# MRCS-cpNode.net
KiCad netlist of a schematic drawn in EAGLE
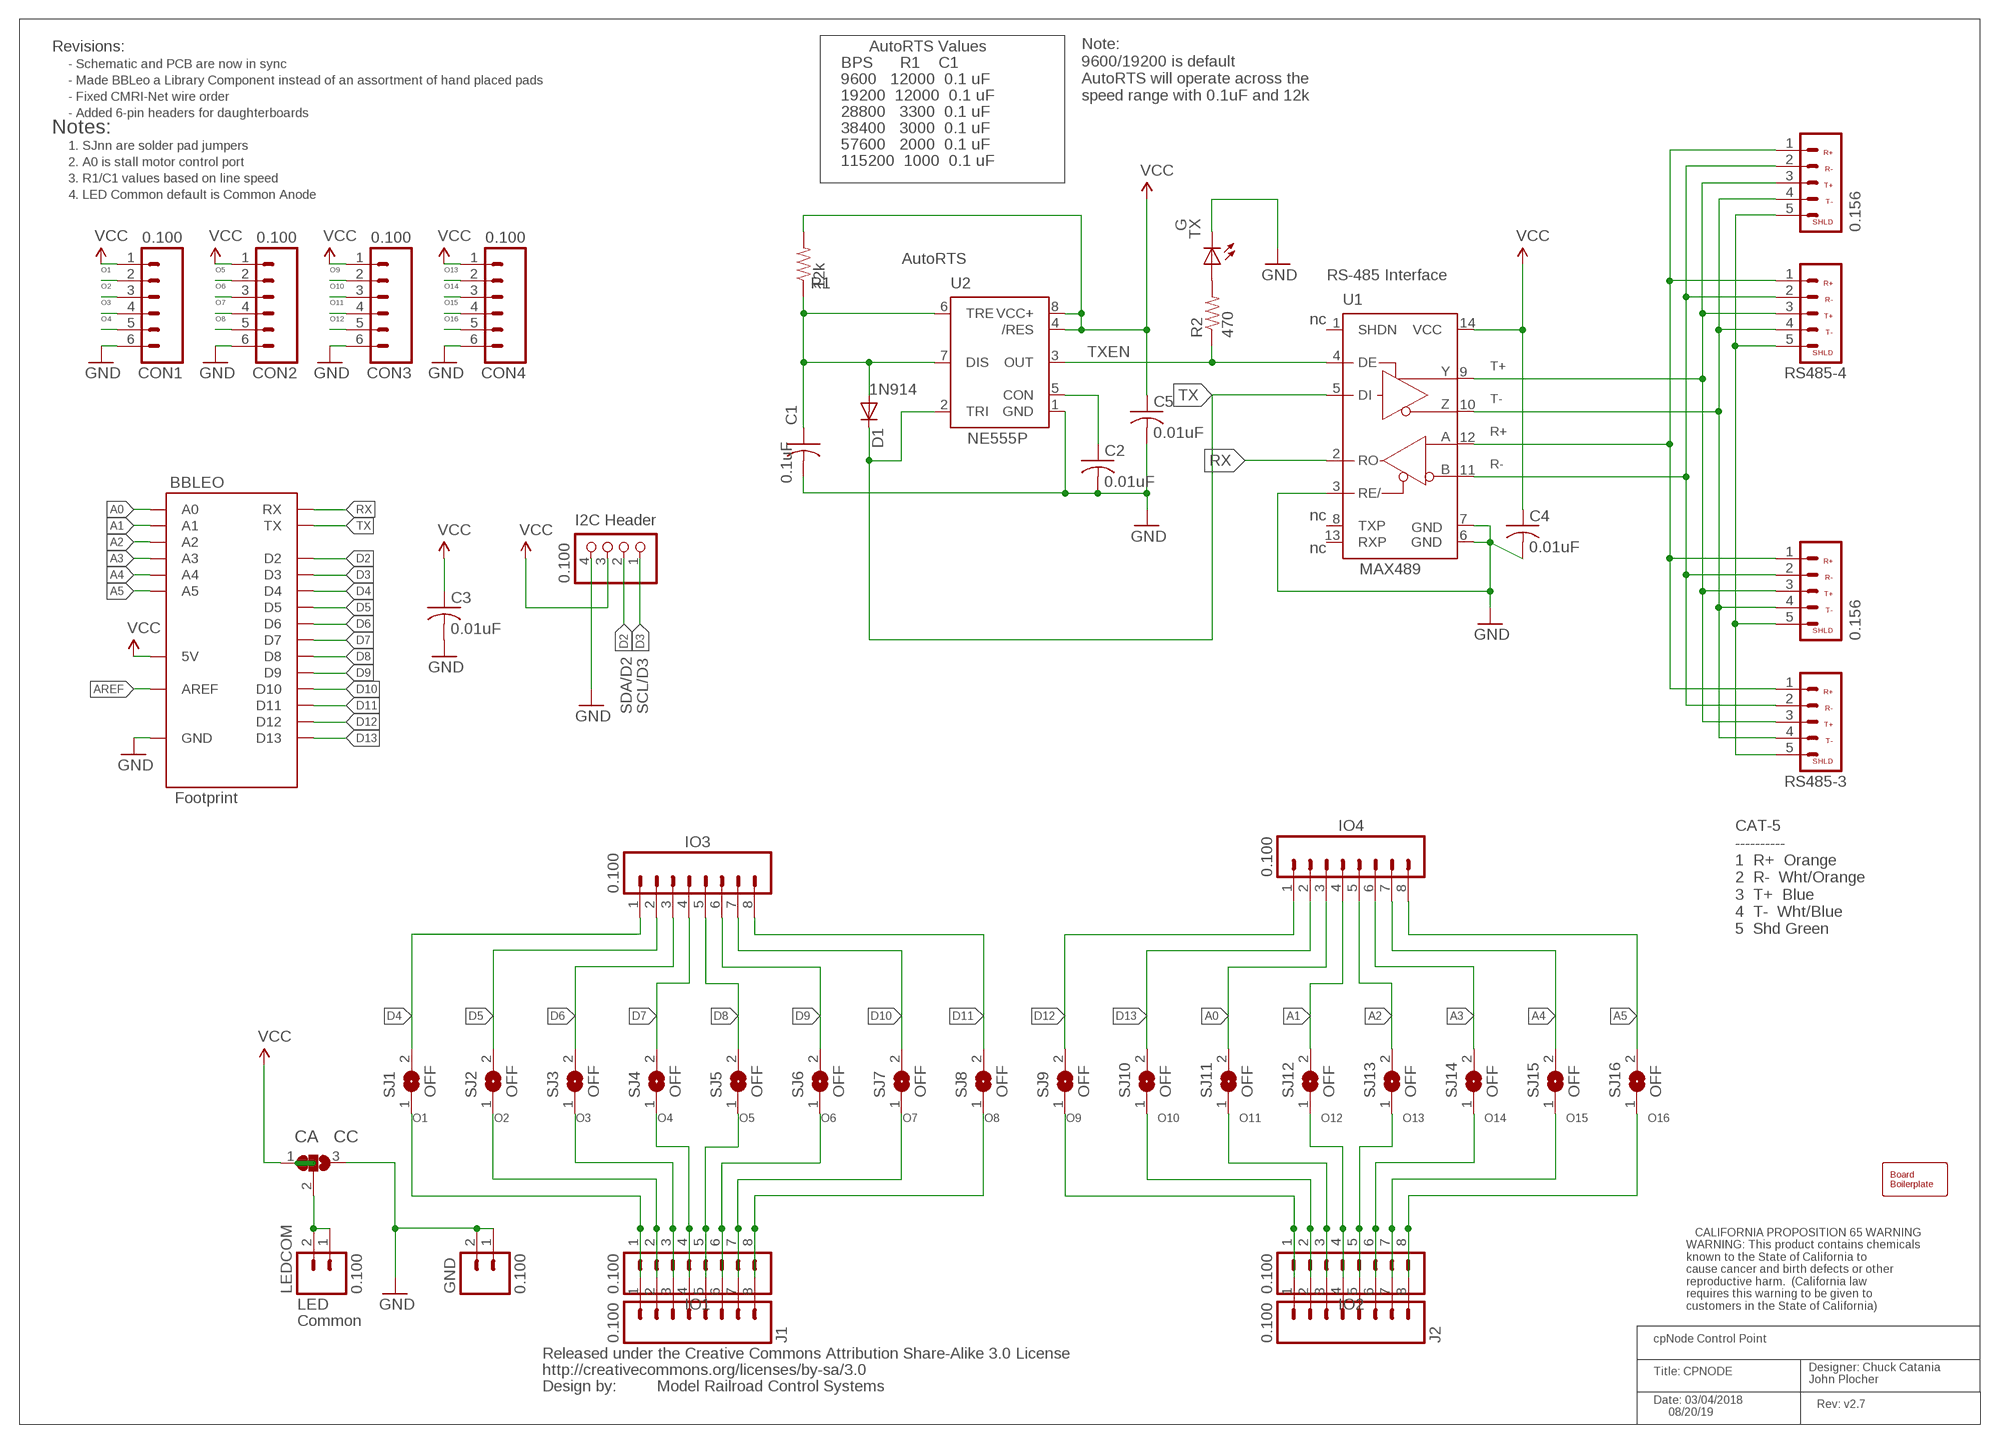
[diagram p0: schematic, sheet 1]

(export (version "E")
  (design (tool "Eeschema 10.0.6"))
  (components
    (comp (ref "BBLEO")
      (value "Footprint")
      (footprint "eagle-import:ARDUINO-BBLEO")
      (libsource (lib "eagle-import") (part "ARDUINO-BBLEO"))
    )
    (comp (ref "BOARD1")
      (value "BOARD")
      (footprint "eagle-import:BOARD-DINRAIL-2.71IN-MRCS")
      (libsource (lib "eagle-import") (part "BOARD69X100MRCS"))
    )
    (comp (ref "C1")
      (value "0.1uF")
      (footprint "eagle-import:C-PTH-0.100")
      (libsource (lib "eagle-import") (part "CAPPTH2"))
    )
    (comp (ref "C2")
      (value "0.01uF")
      (footprint "eagle-import:C-PTH-0.100")
      (libsource (lib "eagle-import") (part "CAPPTH2"))
    )
    (comp (ref "C3")
      (value "0.01uF")
      (footprint "eagle-import:C-PTH-0.100")
      (libsource (lib "eagle-import") (part "CAPPTH2"))
    )
    (comp (ref "C4")
      (value "0.01uF")
      (footprint "eagle-import:C-PTH-0.100")
      (libsource (lib "eagle-import") (part "CAPPTH2"))
    )
    (comp (ref "C5")
      (value "0.01uF")
      (footprint "eagle-import:C-PTH-0.100")
      (libsource (lib "eagle-import") (part "CAPPTH2"))
    )
    (comp (ref "CON1")
      (value "0.100")
      (footprint "eagle-import:1X06-SIP_LOCK")
      (libsource (lib "eagle-import") (part "CONNECTOR-M06SIP_LOCK"))
    )
    (comp (ref "CON2")
      (value "0.100")
      (footprint "eagle-import:1X06-SIP_LOCK")
      (libsource (lib "eagle-import") (part "CONNECTOR-M06SIP_LOCK"))
    )
    (comp (ref "CON3")
      (value "0.100")
      (footprint "eagle-import:1X06-SIP_LOCK")
      (libsource (lib "eagle-import") (part "CONNECTOR-M06SIP_LOCK"))
    )
    (comp (ref "CON4")
      (value "0.100")
      (footprint "eagle-import:1X06-SIP_LOCK")
      (libsource (lib "eagle-import") (part "CONNECTOR-M06SIP_LOCK"))
    )
    (comp (ref "D1")
      (value "1N4148")
      (footprint "eagle-import:DIODE-1N4148")
      (libsource (lib "eagle-import") (part "DIODE1N4148"))
    )
    (comp (ref "GND")
      (value "0.100")
      (footprint "eagle-import:MOLEX-1X2_LOCK")
      (libsource (lib "eagle-import") (part "M02POLAR_LOCK"))
    )
    (comp (ref "I2CHDR")
      (value "0.100")
      (footprint "eagle-import:1X04_90")
      (libsource (lib "eagle-import") (part "PINHD-1X4/90"))
    )
    (comp (ref "IO1")
      (value "0.100")
      (footprint "eagle-import:1X08")
      (libsource (lib "eagle-import") (part "M081X08"))
    )
    (comp (ref "IO2")
      (value "0.100")
      (footprint "eagle-import:1X08")
      (libsource (lib "eagle-import") (part "M081X08"))
    )
    (comp (ref "IO3")
      (value "0.100")
      (footprint "eagle-import:1X08")
      (libsource (lib "eagle-import") (part "M081X08"))
    )
    (comp (ref "IO4")
      (value "0.100")
      (footprint "eagle-import:1X08")
      (libsource (lib "eagle-import") (part "M081X08"))
    )
    (comp (ref "J1")
      (value "0.100")
      (footprint "eagle-import:1X08_LOCK_LONGPADS")
      (libsource (lib "eagle-import") (part "CONNECTOR-M08LOCK_LONGPADS"))
    )
    (comp (ref "J2")
      (value "0.100")
      (footprint "eagle-import:1X08_LOCK_LONGPADS")
      (libsource (lib "eagle-import") (part "CONNECTOR-M08LOCK_LONGPADS"))
    )
    (comp (ref "LEDCOM")
      (value "0.100")
      (footprint "eagle-import:MOLEX-1X2_LOCK")
      (libsource (lib "eagle-import") (part "M02POLAR_LOCK"))
    )
    (comp (ref "P1")
      (value "CA CC")
      (footprint "eagle-import:3P-SMD-2X4.8")
      (libsource (lib "eagle-import") (part "PAD-SOLDERJUMPER-2WAYT"))
    )
    (comp (ref "R1")
      (value "12k")
      (footprint "eagle-import:AXIAL-0.4-RES")
      (libsource (lib "eagle-import") (part "RPTH04"))
    )
    (comp (ref "R2")
      (value "470")
      (footprint "eagle-import:AXIAL-0.4-RES")
      (libsource (lib "eagle-import") (part "RPTH04"))
    )
    (comp (ref "RS485-1")
      (value "0.156")
      (footprint "eagle-import:KK-156-5")
      (libsource (lib "eagle-import") (part "CONNECTOR-CMRINET.156"))
    )
    (comp (ref "RS485-2")
      (value "0.156")
      (footprint "eagle-import:KK-156-5")
      (libsource (lib "eagle-import") (part "CONNECTOR-CMRINET.156"))
    )
    (comp (ref "RS485-3")
      (value "3.5mm")
      (footprint "eagle-import:CMRINET-3.5MM")
      (libsource (lib "eagle-import") (part "CONNECTOR-CMRINET3.5MM"))
    )
    (comp (ref "RS485-4")
      (value "3.5mm")
      (footprint "eagle-import:CMRINET-3.5MM")
      (libsource (lib "eagle-import") (part "CONNECTOR-CMRINET3.5MM"))
    )
    (comp (ref "SJ1")
      (value "OFF")
      (footprint "eagle-import:SJ")
      (libsource (lib "eagle-import") (part "SJ"))
    )
    (comp (ref "SJ2")
      (value "OFF")
      (footprint "eagle-import:SJ")
      (libsource (lib "eagle-import") (part "SJ"))
    )
    (comp (ref "SJ3")
      (value "OFF")
      (footprint "eagle-import:SJ")
      (libsource (lib "eagle-import") (part "SJ"))
    )
    (comp (ref "SJ4")
      (value "OFF")
      (footprint "eagle-import:SJ")
      (libsource (lib "eagle-import") (part "SJ"))
    )
    (comp (ref "SJ5")
      (value "OFF")
      (footprint "eagle-import:SJ")
      (libsource (lib "eagle-import") (part "SJ"))
    )
    (comp (ref "SJ6")
      (value "OFF")
      (footprint "eagle-import:SJ")
      (libsource (lib "eagle-import") (part "SJ"))
    )
    (comp (ref "SJ7")
      (value "OFF")
      (footprint "eagle-import:SJ")
      (libsource (lib "eagle-import") (part "SJ"))
    )
    (comp (ref "SJ8")
      (value "OFF")
      (footprint "eagle-import:SJ")
      (libsource (lib "eagle-import") (part "SJ"))
    )
    (comp (ref "SJ9")
      (value "OFF")
      (footprint "eagle-import:SJ")
      (libsource (lib "eagle-import") (part "SJ"))
    )
    (comp (ref "SJ10")
      (value "OFF")
      (footprint "eagle-import:SJ")
      (libsource (lib "eagle-import") (part "SJ"))
    )
    (comp (ref "SJ11")
      (value "OFF")
      (footprint "eagle-import:SJ")
      (libsource (lib "eagle-import") (part "SJ"))
    )
    (comp (ref "SJ12")
      (value "OFF")
      (footprint "eagle-import:SJ")
      (libsource (lib "eagle-import") (part "SJ"))
    )
    (comp (ref "SJ13")
      (value "OFF")
      (footprint "eagle-import:SJ")
      (libsource (lib "eagle-import") (part "SJ"))
    )
    (comp (ref "SJ14")
      (value "OFF")
      (footprint "eagle-import:SJ")
      (libsource (lib "eagle-import") (part "SJ"))
    )
    (comp (ref "SJ15")
      (value "OFF")
      (footprint "eagle-import:SJ")
      (libsource (lib "eagle-import") (part "SJ"))
    )
    (comp (ref "SJ16")
      (value "OFF")
      (footprint "eagle-import:SJ")
      (libsource (lib "eagle-import") (part "SJ"))
    )
    (comp (ref "TX")
      (value "G")
      (footprint "eagle-import:LED3MM")
      (libsource (lib "eagle-import") (part "LEDLED3MM"))
    )
    (comp (ref "U$1")
      (value "CREATIVE_COMMONS")
      (footprint "eagle-import:CREATIVE_COMMONS")
      (libsource (lib "eagle-import") (part "CREATIVE_COMMONS"))
    )
    (comp (ref "U$2")
      (value "Prop65")
      (footprint "eagle-import:CA-PROP65WARNING")
      (libsource (lib "eagle-import") (part "CA-PROP65WARNING"))
    )
    (comp (ref "U1")
      (value "MAX3465CPD")
      (footprint "eagle-import:DIL14")
      (fields (field (name "MPN") "MAX3465CPD+"))
      (libsource (lib "eagle-import") (part "MAX346PD5C"))
    )
    (comp (ref "U2")
      (value "NE555P")
      (footprint "eagle-import:DIL-08")
      (fields (field (name "MF") "Arrow Electronics") (field (name "MPN") "NE555N"))
      (libsource (lib "eagle-import") (part "NE555P"))
    )
  )
  (nets
    (net (code "1") (name "/O1") (class "Default")
      (node (ref "CON1") (pin "2") (pinfunction "2_2") (pintype "passive"))
      (node (ref "IO1") (pin "1") (pinfunction "1_1") (pintype "passive"))
      (node (ref "J1") (pin "1") (pinfunction "1_1") (pintype "passive"))
      (node (ref "SJ1") (pin "1") (pinfunction "1_1") (pintype "passive"))
    )
    (net (code "2") (name "/O2") (class "Default")
      (node (ref "CON1") (pin "3") (pinfunction "3_3") (pintype "passive"))
      (node (ref "IO1") (pin "2") (pinfunction "2_2") (pintype "passive"))
      (node (ref "J1") (pin "2") (pinfunction "2_2") (pintype "passive"))
      (node (ref "SJ2") (pin "1") (pinfunction "1_1") (pintype "passive"))
    )
    (net (code "3") (name "/O3") (class "Default")
      (node (ref "CON1") (pin "4") (pinfunction "4_4") (pintype "passive"))
      (node (ref "IO1") (pin "3") (pinfunction "3_3") (pintype "passive"))
      (node (ref "J1") (pin "3") (pinfunction "3_3") (pintype "passive"))
      (node (ref "SJ3") (pin "1") (pinfunction "1_1") (pintype "passive"))
    )
    (net (code "4") (name "/O4") (class "Default")
      (node (ref "CON1") (pin "5") (pinfunction "5_5") (pintype "passive"))
      (node (ref "IO1") (pin "4") (pinfunction "4_4") (pintype "passive"))
      (node (ref "J1") (pin "4") (pinfunction "4_4") (pintype "passive"))
      (node (ref "SJ4") (pin "1") (pinfunction "1_1") (pintype "passive"))
    )
    (net (code "5") (name "/O5") (class "Default")
      (node (ref "CON2") (pin "2") (pinfunction "2_2") (pintype "passive"))
      (node (ref "IO1") (pin "5") (pinfunction "5_5") (pintype "passive"))
      (node (ref "J1") (pin "5") (pinfunction "5_5") (pintype "passive"))
      (node (ref "SJ5") (pin "1") (pinfunction "1_1") (pintype "passive"))
    )
    (net (code "6") (name "/O6") (class "Default")
      (node (ref "CON2") (pin "3") (pinfunction "3_3") (pintype "passive"))
      (node (ref "IO1") (pin "6") (pinfunction "6_6") (pintype "passive"))
      (node (ref "J1") (pin "6") (pinfunction "6_6") (pintype "passive"))
      (node (ref "SJ6") (pin "1") (pinfunction "1_1") (pintype "passive"))
    )
    (net (code "7") (name "/O7") (class "Default")
      (node (ref "CON2") (pin "4") (pinfunction "4_4") (pintype "passive"))
      (node (ref "IO1") (pin "7") (pinfunction "7_7") (pintype "passive"))
      (node (ref "J1") (pin "7") (pinfunction "7_7") (pintype "passive"))
      (node (ref "SJ7") (pin "1") (pinfunction "1_1") (pintype "passive"))
    )
    (net (code "8") (name "/O8") (class "Default")
      (node (ref "CON2") (pin "5") (pinfunction "5_5") (pintype "passive"))
      (node (ref "IO1") (pin "8") (pinfunction "8_8") (pintype "passive"))
      (node (ref "J1") (pin "8") (pinfunction "8_8") (pintype "passive"))
      (node (ref "SJ8") (pin "1") (pinfunction "1_1") (pintype "passive"))
    )
    (net (code "9") (name "/O9") (class "Default")
      (node (ref "CON3") (pin "2") (pinfunction "2_2") (pintype "passive"))
      (node (ref "IO2") (pin "1") (pinfunction "1_1") (pintype "passive"))
      (node (ref "J2") (pin "1") (pinfunction "1_1") (pintype "passive"))
      (node (ref "SJ9") (pin "1") (pinfunction "1_1") (pintype "passive"))
    )
    (net (code "10") (name "/O10") (class "Default")
      (node (ref "CON3") (pin "3") (pinfunction "3_3") (pintype "passive"))
      (node (ref "IO2") (pin "2") (pinfunction "2_2") (pintype "passive"))
      (node (ref "J2") (pin "2") (pinfunction "2_2") (pintype "passive"))
      (node (ref "SJ10") (pin "1") (pinfunction "1_1") (pintype "passive"))
    )
    (net (code "11") (name "/O11") (class "Default")
      (node (ref "CON3") (pin "4") (pinfunction "4_4") (pintype "passive"))
      (node (ref "IO2") (pin "3") (pinfunction "3_3") (pintype "passive"))
      (node (ref "J2") (pin "3") (pinfunction "3_3") (pintype "passive"))
      (node (ref "SJ11") (pin "1") (pinfunction "1_1") (pintype "passive"))
    )
    (net (code "12") (name "/O12") (class "Default")
      (node (ref "CON3") (pin "5") (pinfunction "5_5") (pintype "passive"))
      (node (ref "IO2") (pin "4") (pinfunction "4_4") (pintype "passive"))
      (node (ref "J2") (pin "4") (pinfunction "4_4") (pintype "passive"))
      (node (ref "SJ12") (pin "1") (pinfunction "1_1") (pintype "passive"))
    )
    (net (code "13") (name "/O13") (class "Default")
      (node (ref "CON4") (pin "2") (pinfunction "2_2") (pintype "passive"))
      (node (ref "IO2") (pin "5") (pinfunction "5_5") (pintype "passive"))
      (node (ref "J2") (pin "5") (pinfunction "5_5") (pintype "passive"))
      (node (ref "SJ13") (pin "1") (pinfunction "1_1") (pintype "passive"))
    )
    (net (code "14") (name "/O14") (class "Default")
      (node (ref "CON4") (pin "3") (pinfunction "3_3") (pintype "passive"))
      (node (ref "IO2") (pin "6") (pinfunction "6_6") (pintype "passive"))
      (node (ref "J2") (pin "6") (pinfunction "6_6") (pintype "passive"))
      (node (ref "SJ14") (pin "1") (pinfunction "1_1") (pintype "passive"))
    )
    (net (code "15") (name "/O15") (class "Default")
      (node (ref "CON4") (pin "4") (pinfunction "4_4") (pintype "passive"))
      (node (ref "IO2") (pin "7") (pinfunction "7_7") (pintype "passive"))
      (node (ref "J2") (pin "7") (pinfunction "7_7") (pintype "passive"))
      (node (ref "SJ15") (pin "1") (pinfunction "1_1") (pintype "passive"))
    )
    (net (code "16") (name "/O16") (class "Default")
      (node (ref "CON4") (pin "5") (pinfunction "5_5") (pintype "passive"))
      (node (ref "IO2") (pin "8") (pinfunction "8_8") (pintype "passive"))
      (node (ref "J2") (pin "8") (pinfunction "8_8") (pintype "passive"))
      (node (ref "SJ16") (pin "1") (pinfunction "1_1") (pintype "passive"))
    )
    (net (code "17") (name "A0") (class "Default")
      (node (ref "BBLEO") (pin "A0") (pinfunction "A0_A0") (pintype "bidirectional"))
      (node (ref "IO4") (pin "3") (pinfunction "3_3") (pintype "passive"))
      (node (ref "SJ11") (pin "2") (pinfunction "2_2") (pintype "passive"))
    )
    (net (code "18") (name "A1") (class "Default")
      (node (ref "BBLEO") (pin "A1") (pinfunction "A1_A1") (pintype "bidirectional"))
      (node (ref "IO4") (pin "4") (pinfunction "4_4") (pintype "passive"))
      (node (ref "SJ12") (pin "2") (pinfunction "2_2") (pintype "passive"))
    )
    (net (code "19") (name "A2") (class "Default")
      (node (ref "BBLEO") (pin "A2") (pinfunction "A2_A2") (pintype "bidirectional"))
      (node (ref "IO4") (pin "5") (pinfunction "5_5") (pintype "passive"))
      (node (ref "SJ13") (pin "2") (pinfunction "2_2") (pintype "passive"))
    )
    (net (code "20") (name "A3") (class "Default")
      (node (ref "BBLEO") (pin "A3") (pinfunction "A3_A3") (pintype "bidirectional"))
      (node (ref "IO4") (pin "6") (pinfunction "6_6") (pintype "passive"))
      (node (ref "SJ14") (pin "2") (pinfunction "2_2") (pintype "passive"))
    )
    (net (code "21") (name "A4") (class "Default")
      (node (ref "BBLEO") (pin "A4") (pinfunction "A4_A4") (pintype "bidirectional"))
      (node (ref "IO4") (pin "7") (pinfunction "7_7") (pintype "passive"))
      (node (ref "SJ15") (pin "2") (pinfunction "2_2") (pintype "passive"))
    )
    (net (code "22") (name "A5") (class "Default")
      (node (ref "BBLEO") (pin "A5") (pinfunction "A5_A5") (pintype "bidirectional"))
      (node (ref "IO4") (pin "8") (pinfunction "8_8") (pintype "passive"))
      (node (ref "SJ16") (pin "2") (pinfunction "2_2") (pintype "passive"))
    )
    (net (code "23") (name "AREF") (class "Default")
      (node (ref "BBLEO") (pin "AR") (pinfunction "AREF_AR") (pintype "bidirectional"))
    )
    (net (code "24") (name "D2") (class "Default")
      (node (ref "BBLEO") (pin "SDA") (pinfunction "D2_SDA") (pintype "bidirectional"))
      (node (ref "I2CHDR") (pin "2") (pinfunction "2_2") (pintype "passive"))
    )
    (net (code "25") (name "D3") (class "Default")
      (node (ref "BBLEO") (pin "SCL") (pinfunction "D3_SCL") (pintype "bidirectional"))
      (node (ref "I2CHDR") (pin "1") (pinfunction "1_1") (pintype "passive"))
    )
    (net (code "26") (name "D4") (class "Default")
      (node (ref "BBLEO") (pin "D4") (pinfunction "D4_D4") (pintype "bidirectional"))
      (node (ref "IO3") (pin "1") (pinfunction "1_1") (pintype "passive"))
      (node (ref "SJ1") (pin "2") (pinfunction "2_2") (pintype "passive"))
    )
    (net (code "27") (name "D5") (class "Default")
      (node (ref "BBLEO") (pin "D5") (pinfunction "D5_D5") (pintype "bidirectional"))
      (node (ref "IO3") (pin "2") (pinfunction "2_2") (pintype "passive"))
      (node (ref "SJ2") (pin "2") (pinfunction "2_2") (pintype "passive"))
    )
    (net (code "28") (name "D6") (class "Default")
      (node (ref "BBLEO") (pin "D6") (pinfunction "D6_D6") (pintype "bidirectional"))
      (node (ref "IO3") (pin "3") (pinfunction "3_3") (pintype "passive"))
      (node (ref "SJ3") (pin "2") (pinfunction "2_2") (pintype "passive"))
    )
    (net (code "29") (name "D7") (class "Default")
      (node (ref "BBLEO") (pin "D7") (pinfunction "D7_D7") (pintype "bidirectional"))
      (node (ref "IO3") (pin "4") (pinfunction "4_4") (pintype "passive"))
      (node (ref "SJ4") (pin "2") (pinfunction "2_2") (pintype "passive"))
    )
    (net (code "30") (name "D8") (class "Default")
      (node (ref "BBLEO") (pin "D8") (pinfunction "D8_D8") (pintype "bidirectional"))
      (node (ref "IO3") (pin "5") (pinfunction "5_5") (pintype "passive"))
      (node (ref "SJ5") (pin "2") (pinfunction "2_2") (pintype "passive"))
    )
    (net (code "31") (name "D9") (class "Default")
      (node (ref "BBLEO") (pin "D9") (pinfunction "D9_D9") (pintype "bidirectional"))
      (node (ref "IO3") (pin "6") (pinfunction "6_6") (pintype "passive"))
      (node (ref "SJ6") (pin "2") (pinfunction "2_2") (pintype "passive"))
    )
    (net (code "32") (name "D10") (class "Default")
      (node (ref "BBLEO") (pin "D10") (pinfunction "D10_D10") (pintype "bidirectional"))
      (node (ref "IO3") (pin "7") (pinfunction "7_7") (pintype "passive"))
      (node (ref "SJ7") (pin "2") (pinfunction "2_2") (pintype "passive"))
    )
    (net (code "33") (name "D11") (class "Default")
      (node (ref "BBLEO") (pin "D11") (pinfunction "D11_D11") (pintype "bidirectional"))
      (node (ref "IO3") (pin "8") (pinfunction "8_8") (pintype "passive"))
      (node (ref "SJ8") (pin "2") (pinfunction "2_2") (pintype "passive"))
    )
    (net (code "34") (name "D12") (class "Default")
      (node (ref "BBLEO") (pin "D12") (pinfunction "D12_D12") (pintype "bidirectional"))
      (node (ref "IO4") (pin "1") (pinfunction "1_1") (pintype "passive"))
      (node (ref "SJ9") (pin "2") (pinfunction "2_2") (pintype "passive"))
    )
    (net (code "35") (name "D13") (class "Default")
      (node (ref "BBLEO") (pin "D13") (pinfunction "D13_D13") (pintype "bidirectional"))
      (node (ref "IO4") (pin "2") (pinfunction "2_2") (pintype "passive"))
      (node (ref "SJ10") (pin "2") (pinfunction "2_2") (pintype "passive"))
    )
    (net (code "36") (name "GND") (class "Default")
      (node (ref "BBLEO") (pin "GND@0") (pinfunction "GND_GND@0") (pintype "bidirectional"))
      (node (ref "BBLEO") (pin "GND@1") (pinfunction "GND_GND@1") (pintype "bidirectional"))
      (node (ref "BBLEO") (pin "GND@2") (pinfunction "GND_GND@2") (pintype "bidirectional"))
      (node (ref "BBLEO") (pin "GND@3") (pinfunction "GND_GND@3") (pintype "bidirectional"))
      (node (ref "BBLEO") (pin "GND@4") (pinfunction "GND_GND@4") (pintype "bidirectional"))
      (node (ref "C1") (pin "2") (pinfunction "2_2") (pintype "passive"))
      (node (ref "C2") (pin "2") (pinfunction "2_2") (pintype "passive"))
      (node (ref "C3") (pin "2") (pinfunction "2_2") (pintype "passive"))
      (node (ref "C4") (pin "2") (pinfunction "2_2") (pintype "passive"))
      (node (ref "C5") (pin "2") (pinfunction "2_2") (pintype "passive"))
      (node (ref "CON1") (pin "6") (pinfunction "6_6") (pintype "passive"))
      (node (ref "CON2") (pin "6") (pinfunction "6_6") (pintype "passive"))
      (node (ref "CON3") (pin "6") (pinfunction "6_6") (pintype "passive"))
      (node (ref "CON4") (pin "6") (pinfunction "6_6") (pintype "passive"))
      (node (ref "GND") (pin "1") (pinfunction "1_1") (pintype "passive"))
      (node (ref "GND") (pin "2") (pinfunction "2_2") (pintype "passive"))
      (node (ref "I2CHDR") (pin "4") (pinfunction "4_4") (pintype "passive"))
      (node (ref "P1") (pin "3") (pinfunction "3_3") (pintype "passive"))
      (node (ref "TX") (pin "K") (pinfunction "C_K") (pintype "passive"))
      (node (ref "U1") (pin "3") (pinfunction "RE/_3") (pintype "input"))
      (node (ref "U1") (pin "6") (pinfunction "GND_6") (pintype "power_in"))
      (node (ref "U1") (pin "7") (pinfunction "GND_7") (pintype "power_in"))
      (node (ref "U2") (pin "1") (pinfunction "GND_1") (pintype "power_in"))
    )
    (net (code "37") (name "Net-(LEDCOM-Pad1)") (class "Default")
      (node (ref "LEDCOM") (pin "1") (pinfunction "1_1") (pintype "passive"))
      (node (ref "LEDCOM") (pin "2") (pinfunction "2_2") (pintype "passive"))
      (node (ref "P1") (pin "2") (pinfunction "2_2") (pintype "passive"))
    )
    (net (code "38") (name "Net-(R1-1)") (class "Default")
      (node (ref "C1") (pin "1") (pinfunction "1_1") (pintype "passive"))
      (node (ref "D1") (pin "A") (pinfunction "A_A") (pintype "passive"))
      (node (ref "R1") (pin "P$1") (pinfunction "1_P$1") (pintype "passive"))
      (node (ref "U2") (pin "6") (pinfunction "TRE_6") (pintype "input"))
      (node (ref "U2") (pin "7") (pinfunction "DIS_7") (pintype "input"))
    )
    (net (code "39") (name "Net-(R2-1)") (class "Default")
      (node (ref "R2") (pin "P$1") (pinfunction "1_P$1") (pintype "passive"))
      (node (ref "U1") (pin "4") (pinfunction "DE_4") (pintype "input"))
      (node (ref "U2") (pin "3") (pinfunction "OUT_3") (pintype "output"))
    )
    (net (code "40") (name "Net-(R2-2)") (class "Default")
      (node (ref "R2") (pin "P$2") (pinfunction "2_P$2") (pintype "passive"))
      (node (ref "TX") (pin "A") (pinfunction "A_A") (pintype "passive"))
    )
    (net (code "41") (name "Net-(RS485-1-Pad5)") (class "Default")
      (node (ref "RS485-1") (pin "5") (pinfunction "5_5") (pintype "passive"))
      (node (ref "RS485-2") (pin "5") (pinfunction "5_5") (pintype "passive"))
      (node (ref "RS485-3") (pin "5") (pinfunction "5_5") (pintype "passive"))
      (node (ref "RS485-4") (pin "5") (pinfunction "5_5") (pintype "passive"))
    )
    (net (code "42") (name "Net-(U1-A)") (class "Default")
      (node (ref "RS485-1") (pin "1") (pinfunction "1_1") (pintype "passive"))
      (node (ref "RS485-2") (pin "1") (pinfunction "1_1") (pintype "passive"))
      (node (ref "RS485-3") (pin "1") (pinfunction "1_1") (pintype "passive"))
      (node (ref "RS485-4") (pin "1") (pinfunction "1_1") (pintype "passive"))
      (node (ref "U1") (pin "12") (pinfunction "A_12") (pintype "input"))
    )
    (net (code "43") (name "Net-(U1-B)") (class "Default")
      (node (ref "RS485-1") (pin "2") (pinfunction "2_2") (pintype "passive"))
      (node (ref "RS485-2") (pin "2") (pinfunction "2_2") (pintype "passive"))
      (node (ref "RS485-3") (pin "2") (pinfunction "2_2") (pintype "passive"))
      (node (ref "RS485-4") (pin "2") (pinfunction "2_2") (pintype "passive"))
      (node (ref "U1") (pin "11") (pinfunction "B_11") (pintype "input"))
    )
    (net (code "44") (name "Net-(U1-Y)") (class "Default")
      (node (ref "RS485-1") (pin "3") (pinfunction "3_3") (pintype "passive"))
      (node (ref "RS485-2") (pin "3") (pinfunction "3_3") (pintype "passive"))
      (node (ref "RS485-3") (pin "3") (pinfunction "3_3") (pintype "passive"))
      (node (ref "RS485-4") (pin "3") (pinfunction "3_3") (pintype "passive"))
      (node (ref "U1") (pin "9") (pinfunction "Y_9") (pintype "output"))
    )
    (net (code "45") (name "Net-(U1-Z)") (class "Default")
      (node (ref "RS485-1") (pin "4") (pinfunction "4_4") (pintype "passive"))
      (node (ref "RS485-2") (pin "4") (pinfunction "4_4") (pintype "passive"))
      (node (ref "RS485-3") (pin "4") (pinfunction "4_4") (pintype "passive"))
      (node (ref "RS485-4") (pin "4") (pinfunction "4_4") (pintype "passive"))
      (node (ref "U1") (pin "10") (pinfunction "Z_10") (pintype "output"))
    )
    (net (code "46") (name "Net-(U2-CON)") (class "Default")
      (node (ref "C2") (pin "1") (pinfunction "1_1") (pintype "passive"))
      (node (ref "U2") (pin "5") (pinfunction "CON_5") (pintype "input"))
    )
    (net (code "47") (name "RX") (class "Default")
      (node (ref "BBLEO") (pin "RX") (pinfunction "RX_RX") (pintype "bidirectional"))
      (node (ref "U1") (pin "2") (pinfunction "RO_2") (pintype "output"))
    )
    (net (code "48") (name "TX") (class "Default")
      (node (ref "BBLEO") (pin "TX") (pinfunction "TX_TX") (pintype "bidirectional"))
      (node (ref "D1") (pin "C") (pinfunction "C_C") (pintype "passive"))
      (node (ref "U1") (pin "5") (pinfunction "DI_5") (pintype "input"))
      (node (ref "U2") (pin "2") (pinfunction "TRI_2") (pintype "input"))
    )
    (net (code "49") (name "VCC") (class "Default")
      (node (ref "BBLEO") (pin "+5V@1") (pinfunction "5V_+5V@1") (pintype "bidirectional"))
      (node (ref "BBLEO") (pin "+5V@2") (pinfunction "5V_+5V@2") (pintype "bidirectional"))
      (node (ref "BBLEO") (pin "+5V@3") (pinfunction "5V_+5V@3") (pintype "bidirectional"))
      (node (ref "BBLEO") (pin "+5V@4") (pinfunction "5V_+5V@4") (pintype "bidirectional"))
      (node (ref "C3") (pin "1") (pinfunction "1_1") (pintype "passive"))
      (node (ref "C4") (pin "1") (pinfunction "1_1") (pintype "passive"))
      (node (ref "C5") (pin "1") (pinfunction "1_1") (pintype "passive"))
      (node (ref "CON1") (pin "1") (pinfunction "1_1") (pintype "passive"))
      (node (ref "CON2") (pin "1") (pinfunction "1_1") (pintype "passive"))
      (node (ref "CON3") (pin "1") (pinfunction "1_1") (pintype "passive"))
      (node (ref "CON4") (pin "1") (pinfunction "1_1") (pintype "passive"))
      (node (ref "I2CHDR") (pin "3") (pinfunction "3_3") (pintype "passive"))
      (node (ref "P1") (pin "1") (pinfunction "1_1") (pintype "passive"))
      (node (ref "R1") (pin "P$2") (pinfunction "2_P$2") (pintype "passive"))
      (node (ref "U1") (pin "14") (pinfunction "VCC_14") (pintype "power_in"))
      (node (ref "U2") (pin "4") (pinfunction "/RES_4") (pintype "input"))
      (node (ref "U2") (pin "8") (pinfunction "VCC+_8") (pintype "power_in"))
    )
    (net (code "50") (name "unconnected-(U1-RXP-Pad13)") (class "Default")
      (node (ref "U1") (pin "13") (pinfunction "RXP_13") (pintype "passive"))
    )
    (net (code "51") (name "unconnected-(U1-SHDN-Pad1)") (class "Default")
      (node (ref "U1") (pin "1") (pinfunction "SHDN_1") (pintype "input"))
    )
    (net (code "52") (name "unconnected-(U1-TXP-Pad8)") (class "Default")
      (node (ref "U1") (pin "8") (pinfunction "TXP_8") (pintype "passive"))
    )
  )
)
